# Audio.net
KiCad netlist of a schematic drawn in Altium Designer
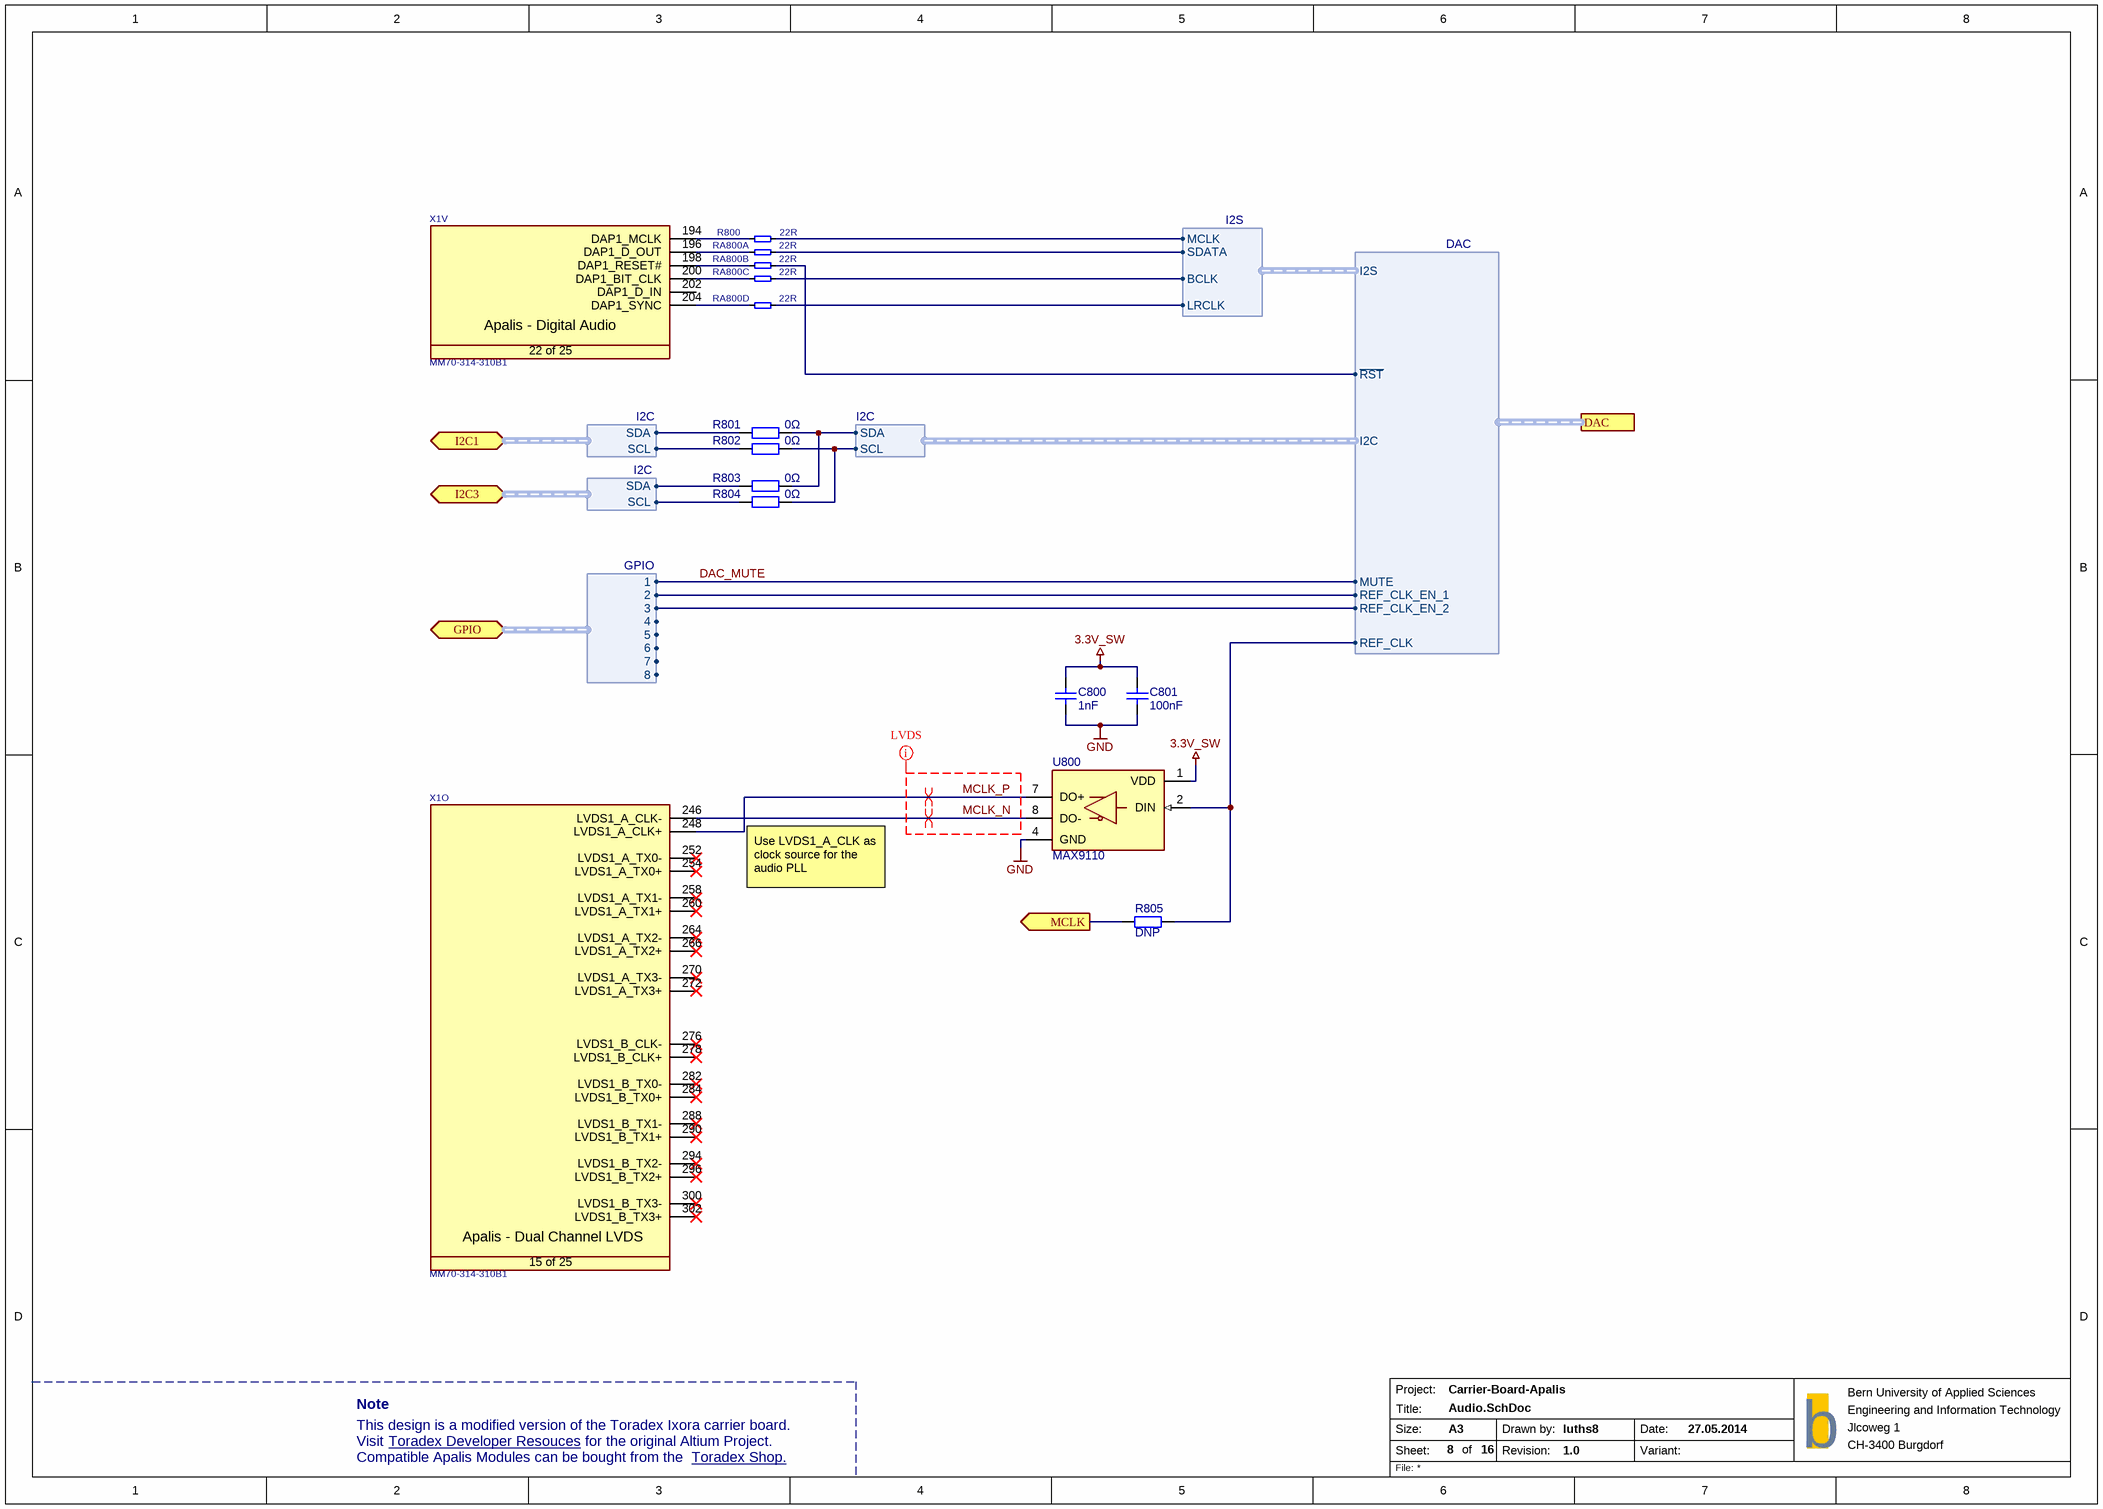
[diagram p0: Audio.SchDoc]

(export (version "E")
  (design (tool "Eeschema 10.0.6"))
  (components
    (comp (ref "C800")
      (value "1nF")
      (footprint "SMD0603CAP")
      (description "Ceramic Capacitor")
      (libsource (lib "Audio-Streamer") (part "Capacitor Ceramic"))
    )
    (comp (ref "C801")
      (value "100nF")
      (footprint "SMD0603CAP")
      (description "Ceramic Capacitor")
      (libsource (lib "Audio-Streamer") (part "Capacitor Ceramic"))
    )
    (comp (ref "R800")
      (value "22R")
      (footprint "SMD0603RES")
      (description "Resistor 22 ohm 63mW 5% 0603")
      (fields (field (name "TOLERANCE") "5%"))
      (libsource (lib "Ixora") (part "R-22R-63mW-5%-0402"))
    )
    (comp (ref "R801")
      (value "0Ω")
      (footprint "SMD0603RES")
      (description "Resistor")
      (libsource (lib "Audio-Streamer") (part "Resistor"))
    )
    (comp (ref "R802")
      (value "0Ω")
      (footprint "SMD0603RES")
      (description "Resistor")
      (libsource (lib "Audio-Streamer") (part "Resistor"))
    )
    (comp (ref "R803")
      (value "0Ω")
      (footprint "SMD0603RES")
      (description "Resistor")
      (libsource (lib "Audio-Streamer") (part "Resistor"))
    )
    (comp (ref "R804")
      (value "0Ω")
      (footprint "SMD0603RES")
      (description "Resistor")
      (libsource (lib "Audio-Streamer") (part "Resistor"))
    )
    (comp (ref "R805")
      (value "DNP")
      (footprint "SMD0603RES")
      (description "Resistor")
      (libsource (lib "") (part "Resistor_1"))
    )
    (comp (ref "RA800")
      (value "22R")
      (footprint "T_Resistor_Array_X4")
      (description "Resistor Array 22 R 63mW 5% 1206")
      (fields (field (name "TOLERANCE") "5%"))
      (libsource (lib "Ixora") (part "RA-22R-63mW-5%-1206-div"))
    )
    (comp (ref "U800")
      (value "MAX9110")
      (footprint "SOIC8")
      (description "LVDS Transmitter")
      (fields (field (name "MANUFACTURER PART NO.") "MAX9110ESA+"))
      (libsource (lib "Audio-Streamer") (part "MAX9110"))
    )
    (comp (ref "X1")
      (value "CON-JAE-MM70-314-310B1-314-0.5mm")
      (footprint "T_JAE_MM70-314-310B1")
      (description "MXM3 Connector")
      (fields (field (name "MANUFACTURER PART NO.") "MM70-314-310B1"))
      (libsource (lib "Ixora") (part "CON-JAE-MM70-314-310B1-314-0.5mm"))
    )
  )
  (nets
    (net (code "7") (name "/BCLK") (class "Default")
      (node (ref "RA800") (pin "7") (pinfunction "7_7") (pintype "passive"))
    )
    (net (code "9") (name "/LRCLK") (class "Default")
      (node (ref "RA800") (pin "8") (pinfunction "8_8") (pintype "passive"))
    )
    (net (code "10") (name "/MCLK") (class "Default")
      (node (ref "R805") (pin "2") (pinfunction "2_2") (pintype "passive"))
    )
    (net (code "11") (name "/MCLK_N") (class "Default")
      (node (ref "U800") (pin "8") (pinfunction "DO-_8") (pintype "passive"))
      (node (ref "X1") (pin "246") (pinfunction "LVDS1_A_CLK-_246") (pintype "passive"))
    )
    (net (code "12") (name "/MCLK_P") (class "Default")
      (node (ref "U800") (pin "7") (pinfunction "DO+_7") (pintype "passive"))
      (node (ref "X1") (pin "248") (pinfunction "LVDS1_A_CLK+_248") (pintype "passive"))
    )
    (net (code "13") (name "/REF_CLK") (class "Default")
      (node (ref "R805") (pin "1") (pinfunction "1_1") (pintype "passive"))
      (node (ref "U800") (pin "2") (pinfunction "DIN_2") (pintype "input"))
    )
    (net (code "14") (name "/SDATA") (class "Default")
      (node (ref "RA800") (pin "5") (pinfunction "5_5") (pintype "passive"))
    )
    (net (code "19") (name "/~{RST}") (class "Default")
      (node (ref "RA800") (pin "6") (pinfunction "6_6") (pintype "passive"))
    )
    (net (code "20") (name "3.3V_SW") (class "Default")
      (node (ref "C800") (pin "1") (pinfunction "1_1") (pintype "passive"))
      (node (ref "C801") (pin "1") (pinfunction "1_1") (pintype "passive"))
      (node (ref "U800") (pin "1") (pinfunction "VDD_1") (pintype "power_in"))
    )
    (net (code "21") (name "GND") (class "Default")
      (node (ref "C800") (pin "2") (pinfunction "q_2") (pintype "passive"))
      (node (ref "C801") (pin "2") (pinfunction "q_2") (pintype "passive"))
      (node (ref "U800") (pin "4") (pinfunction "GND_4") (pintype "power_in"))
    )
    (net (code "22") (name "Net-(R801-Pad1)") (class "Default")
      (node (ref "R801") (pin "1") (pinfunction "1_1") (pintype "passive"))
      (node (ref "R803") (pin "1") (pinfunction "1_1") (pintype "passive"))
    )
    (net (code "23") (name "Net-(R802-Pad1)") (class "Default")
      (node (ref "R802") (pin "1") (pinfunction "1_1") (pintype "passive"))
      (node (ref "R804") (pin "1") (pinfunction "1_1") (pintype "passive"))
    )
    (net (code "24") (name "Net-(X1V-DAP1_BIT_CLK)") (class "Default")
      (node (ref "RA800") (pin "3") (pinfunction "3_3") (pintype "passive"))
      (node (ref "X1") (pin "200") (pinfunction "DAP1_BIT_CLK_200") (pintype "passive"))
    )
    (net (code "25") (name "Net-(X1V-DAP1_D_OUT)") (class "Default")
      (node (ref "RA800") (pin "1") (pinfunction "1_1") (pintype "passive"))
      (node (ref "X1") (pin "196") (pinfunction "DAP1_D_OUT_196") (pintype "passive"))
    )
    (net (code "26") (name "Net-(X1V-DAP1_MCLK)") (class "Default")
      (node (ref "R800") (pin "1") (pinfunction "1_1") (pintype "passive"))
      (node (ref "X1") (pin "194") (pinfunction "DAP1_MCLK_194") (pintype "passive"))
    )
    (net (code "27") (name "Net-(X1V-DAP1_RESET#)") (class "Default")
      (node (ref "RA800") (pin "2") (pinfunction "2_2") (pintype "passive"))
      (node (ref "X1") (pin "198") (pinfunction "DAP1_RESET#_198") (pintype "passive"))
    )
    (net (code "28") (name "Net-(X1V-DAP1_SYNC)") (class "Default")
      (node (ref "RA800") (pin "4") (pinfunction "4_4") (pintype "passive"))
      (node (ref "X1") (pin "204") (pinfunction "DAP1_SYNC_204") (pintype "passive"))
    )
    (net (code "29") (name "unconnected-(R800-Pad2)") (class "Default")
      (node (ref "R800") (pin "2") (pinfunction "2_2") (pintype "passive"))
    )
    (net (code "30") (name "unconnected-(R801-Pad2)") (class "Default")
      (node (ref "R801") (pin "2") (pinfunction "2_2") (pintype "passive"))
    )
    (net (code "31") (name "unconnected-(R802-Pad2)") (class "Default")
      (node (ref "R802") (pin "2") (pinfunction "2_2") (pintype "passive"))
    )
    (net (code "32") (name "unconnected-(R803-Pad2)") (class "Default")
      (node (ref "R803") (pin "2") (pinfunction "2_2") (pintype "passive"))
    )
    (net (code "33") (name "unconnected-(R804-Pad2)") (class "Default")
      (node (ref "R804") (pin "2") (pinfunction "2_2") (pintype "passive"))
    )
    (net (code "34") (name "unconnected-(X1O-LVDS1_A_TX0+-Pad254)") (class "Default")
      (node (ref "X1") (pin "254") (pinfunction "LVDS1_A_TX0+_254") (pintype "passive+no_connect"))
    )
    (net (code "35") (name "unconnected-(X1O-LVDS1_A_TX0--Pad252)") (class "Default")
      (node (ref "X1") (pin "252") (pinfunction "LVDS1_A_TX0-_252") (pintype "passive+no_connect"))
    )
    (net (code "36") (name "unconnected-(X1O-LVDS1_A_TX1+-Pad260)") (class "Default")
      (node (ref "X1") (pin "260") (pinfunction "LVDS1_A_TX1+_260") (pintype "passive+no_connect"))
    )
    (net (code "37") (name "unconnected-(X1O-LVDS1_A_TX1--Pad258)") (class "Default")
      (node (ref "X1") (pin "258") (pinfunction "LVDS1_A_TX1-_258") (pintype "passive+no_connect"))
    )
    (net (code "38") (name "unconnected-(X1O-LVDS1_A_TX2+-Pad266)") (class "Default")
      (node (ref "X1") (pin "266") (pinfunction "LVDS1_A_TX2+_266") (pintype "passive+no_connect"))
    )
    (net (code "39") (name "unconnected-(X1O-LVDS1_A_TX2--Pad264)") (class "Default")
      (node (ref "X1") (pin "264") (pinfunction "LVDS1_A_TX2-_264") (pintype "passive+no_connect"))
    )
    (net (code "40") (name "unconnected-(X1O-LVDS1_A_TX3+-Pad272)") (class "Default")
      (node (ref "X1") (pin "272") (pinfunction "LVDS1_A_TX3+_272") (pintype "passive+no_connect"))
    )
    (net (code "41") (name "unconnected-(X1O-LVDS1_A_TX3--Pad270)") (class "Default")
      (node (ref "X1") (pin "270") (pinfunction "LVDS1_A_TX3-_270") (pintype "passive+no_connect"))
    )
    (net (code "42") (name "unconnected-(X1O-LVDS1_B_CLK+-Pad278)") (class "Default")
      (node (ref "X1") (pin "278") (pinfunction "LVDS1_B_CLK+_278") (pintype "passive+no_connect"))
    )
    (net (code "43") (name "unconnected-(X1O-LVDS1_B_CLK--Pad276)") (class "Default")
      (node (ref "X1") (pin "276") (pinfunction "LVDS1_B_CLK-_276") (pintype "passive+no_connect"))
    )
    (net (code "44") (name "unconnected-(X1O-LVDS1_B_TX0+-Pad284)") (class "Default")
      (node (ref "X1") (pin "284") (pinfunction "LVDS1_B_TX0+_284") (pintype "passive+no_connect"))
    )
    (net (code "45") (name "unconnected-(X1O-LVDS1_B_TX0--Pad282)") (class "Default")
      (node (ref "X1") (pin "282") (pinfunction "LVDS1_B_TX0-_282") (pintype "passive+no_connect"))
    )
    (net (code "46") (name "unconnected-(X1O-LVDS1_B_TX1+-Pad290)") (class "Default")
      (node (ref "X1") (pin "290") (pinfunction "LVDS1_B_TX1+_290") (pintype "passive+no_connect"))
    )
    (net (code "47") (name "unconnected-(X1O-LVDS1_B_TX1--Pad288)") (class "Default")
      (node (ref "X1") (pin "288") (pinfunction "LVDS1_B_TX1-_288") (pintype "passive+no_connect"))
    )
    (net (code "48") (name "unconnected-(X1O-LVDS1_B_TX2+-Pad296)") (class "Default")
      (node (ref "X1") (pin "296") (pinfunction "LVDS1_B_TX2+_296") (pintype "passive+no_connect"))
    )
    (net (code "49") (name "unconnected-(X1O-LVDS1_B_TX2--Pad294)") (class "Default")
      (node (ref "X1") (pin "294") (pinfunction "LVDS1_B_TX2-_294") (pintype "passive+no_connect"))
    )
    (net (code "50") (name "unconnected-(X1O-LVDS1_B_TX3+-Pad302)") (class "Default")
      (node (ref "X1") (pin "302") (pinfunction "LVDS1_B_TX3+_302") (pintype "passive+no_connect"))
    )
    (net (code "51") (name "unconnected-(X1O-LVDS1_B_TX3--Pad300)") (class "Default")
      (node (ref "X1") (pin "300") (pinfunction "LVDS1_B_TX3-_300") (pintype "passive+no_connect"))
    )
    (net (code "52") (name "unconnected-(X1V-DAP1_D_IN-Pad202)") (class "Default")
      (node (ref "X1") (pin "202") (pinfunction "DAP1_D_IN_202") (pintype "passive"))
    )
  )
)
